# M_Pascal_Darmawan_21507334050.net
KiCad netlist of a schematic drawn in EAGLE
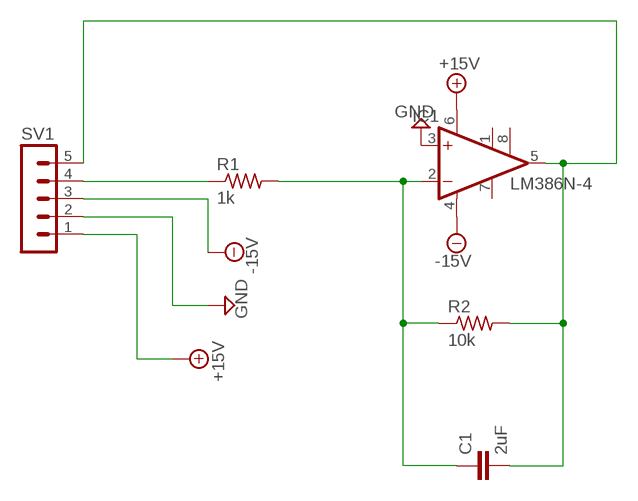
[diagram p0: schematic, sheet 1]

(export (version "E")
  (design (tool "Eeschema 10.0.6"))
  (components
    (comp (ref "C1")
      (value "2uF")
      (footprint "eagle-import:C0603")
      (libsource (lib "eagle-import") (part "C-EUC0603"))
    )
    (comp (ref "IC1")
      (value "LM386N-4")
      (footprint "eagle-import:DIL08")
      (libsource (lib "eagle-import") (part "LM386?-N4"))
    )
    (comp (ref "R1")
      (value "1k")
      (footprint "eagle-import:R0603")
      (libsource (lib "eagle-import") (part "R-US_R0603"))
    )
    (comp (ref "R2")
      (value "10k")
      (footprint "eagle-import:R0603")
      (libsource (lib "eagle-import") (part "R-US_R0603"))
    )
    (comp (ref "SV1")
      (value "MA05-1")
      (footprint "eagle-import:MA05-1")
      (libsource (lib "eagle-import") (part "MA05-1"))
    )
  )
  (nets
    (net (code "1") (name "+15V") (class "Default")
      (node (ref "IC1") (pin "6") (pinfunction "VS_6") (pintype "power_in"))
      (node (ref "SV1") (pin "1") (pinfunction "1_1") (pintype "passive"))
    )
    (net (code "2") (name "-15V") (class "Default")
      (node (ref "IC1") (pin "4") (pinfunction "GND_4") (pintype "power_in"))
      (node (ref "SV1") (pin "3") (pinfunction "3_3") (pintype "passive"))
    )
    (net (code "3") (name "GND") (class "Default")
      (node (ref "IC1") (pin "3") (pinfunction "+IN_3") (pintype "input"))
      (node (ref "SV1") (pin "2") (pinfunction "2_2") (pintype "passive"))
    )
    (net (code "4") (name "Net-(IC1--IN)") (class "Default")
      (node (ref "C1") (pin "1") (pinfunction "1_1") (pintype "passive"))
      (node (ref "IC1") (pin "2") (pinfunction "-IN_2") (pintype "input"))
      (node (ref "R1") (pin "2") (pinfunction "2_2") (pintype "passive"))
      (node (ref "R2") (pin "1") (pinfunction "1_1") (pintype "passive"))
    )
    (net (code "5") (name "Net-(IC1-OUT)") (class "Default")
      (node (ref "C1") (pin "2") (pinfunction "2_2") (pintype "passive"))
      (node (ref "IC1") (pin "5") (pinfunction "OUT_5") (pintype "output"))
      (node (ref "R2") (pin "2") (pinfunction "2_2") (pintype "passive"))
      (node (ref "SV1") (pin "5") (pinfunction "5_5") (pintype "passive"))
    )
    (net (code "6") (name "Net-(R1-Pad1)") (class "Default")
      (node (ref "R1") (pin "1") (pinfunction "1_1") (pintype "passive"))
      (node (ref "SV1") (pin "4") (pinfunction "4_4") (pintype "passive"))
    )
    (net (code "7") (name "unconnected-(IC1-BYPASS-Pad7)") (class "Default")
      (node (ref "IC1") (pin "7") (pinfunction "BYPASS_7") (pintype "passive"))
    )
    (net (code "8") (name "unconnected-(IC1-GAIN-Pad1)") (class "Default")
      (node (ref "IC1") (pin "1") (pinfunction "GAIN_1") (pintype "passive"))
    )
    (net (code "9") (name "unconnected-(IC1-GAIN-Pad8)") (class "Default")
      (node (ref "IC1") (pin "8") (pinfunction "GAIN_8") (pintype "passive"))
    )
  )
)
